# Power_Schematic.net
KiCad netlist of a schematic drawn in EAGLE
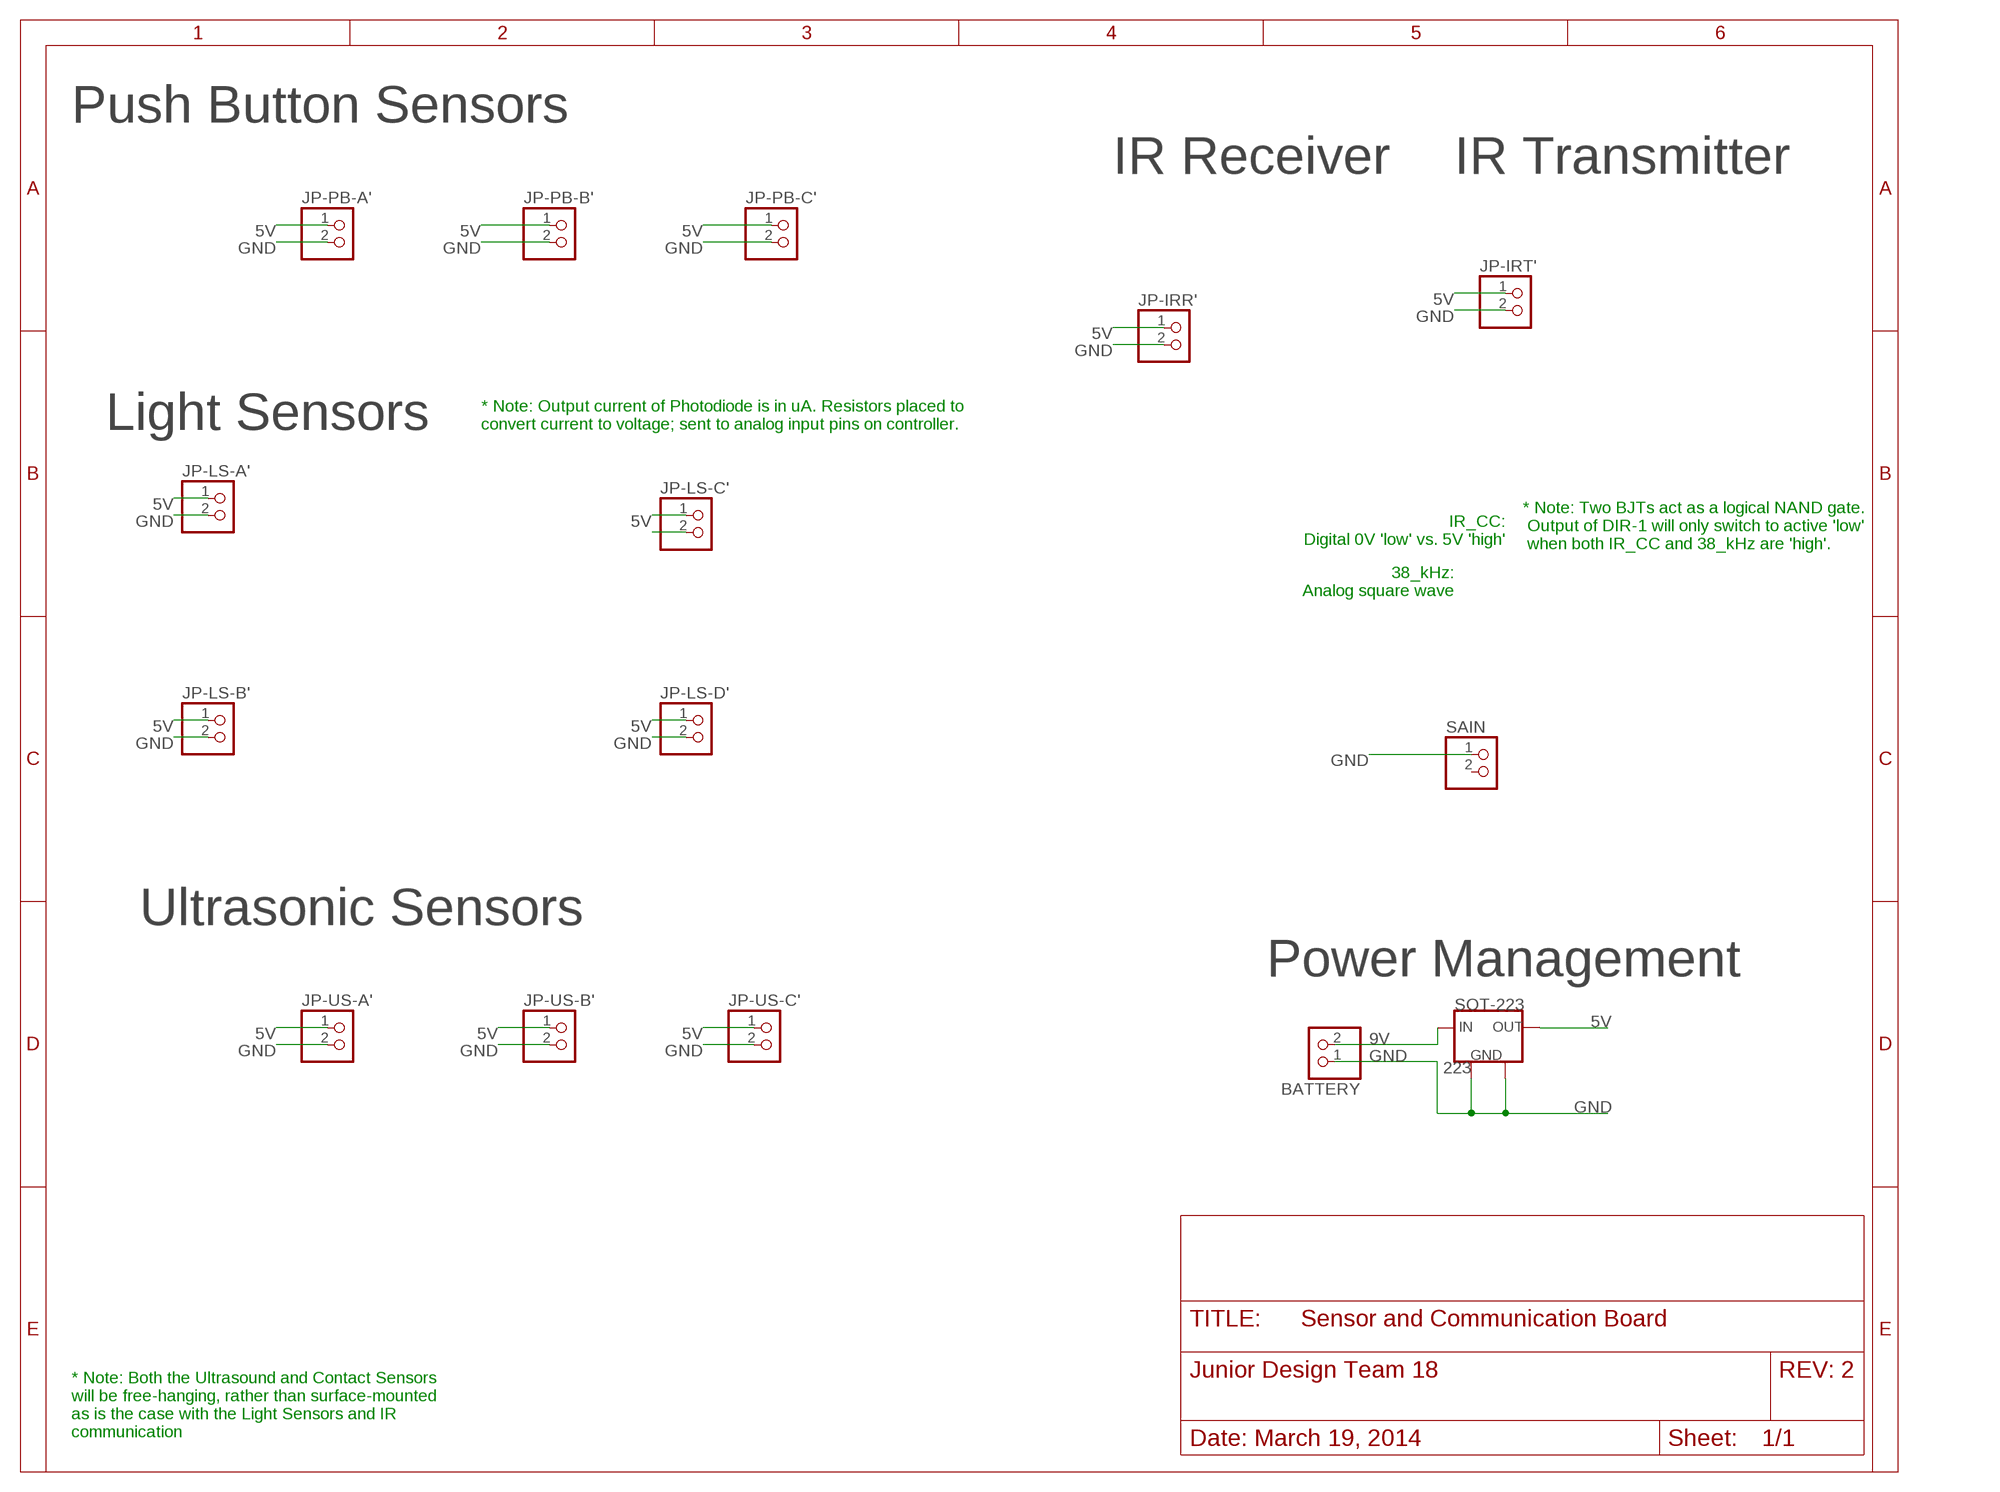
[diagram p0: schematic, sheet 1]

(export (version "E")
  (design (tool "Eeschema 10.0.6"))
  (components
    (comp (ref "BATTERY")
      (value "PINHD-1X2")
      (footprint "eagle-import:1X02")
      (libsource (lib "eagle-import") (part "PINHD-1X2"))
    )
    (comp (ref "JP-IRR'")
      (value "PINHD-1X2")
      (footprint "eagle-import:1X02")
      (libsource (lib "eagle-import") (part "PINHD-1X2"))
    )
    (comp (ref "JP-IRT'")
      (value "PINHD-1X2")
      (footprint "eagle-import:1X02")
      (libsource (lib "eagle-import") (part "PINHD-1X2"))
    )
    (comp (ref "JP-LS-A'")
      (value "PINHD-1X2")
      (footprint "eagle-import:1X02")
      (libsource (lib "eagle-import") (part "PINHD-1X2"))
    )
    (comp (ref "JP-LS-B'")
      (value "PINHD-1X2")
      (footprint "eagle-import:1X02")
      (libsource (lib "eagle-import") (part "PINHD-1X2"))
    )
    (comp (ref "JP-LS-C'")
      (value "PINHD-1X2")
      (footprint "eagle-import:1X02")
      (libsource (lib "eagle-import") (part "PINHD-1X2"))
    )
    (comp (ref "JP-LS-D'")
      (value "PINHD-1X2")
      (footprint "eagle-import:1X02")
      (libsource (lib "eagle-import") (part "PINHD-1X2"))
    )
    (comp (ref "JP-PB-A'")
      (value "PINHD-1X2")
      (footprint "eagle-import:1X02")
      (libsource (lib "eagle-import") (part "PINHD-1X2"))
    )
    (comp (ref "JP-PB-B'")
      (value "PINHD-1X2")
      (footprint "eagle-import:1X02")
      (libsource (lib "eagle-import") (part "PINHD-1X2"))
    )
    (comp (ref "JP-PB-C'")
      (value "PINHD-1X2")
      (footprint "eagle-import:1X02")
      (libsource (lib "eagle-import") (part "PINHD-1X2"))
    )
    (comp (ref "JP-US-A'")
      (value "PINHD-1X2")
      (footprint "eagle-import:1X02")
      (libsource (lib "eagle-import") (part "PINHD-1X2"))
    )
    (comp (ref "JP-US-B'")
      (value "PINHD-1X2")
      (footprint "eagle-import:1X02")
      (libsource (lib "eagle-import") (part "PINHD-1X2"))
    )
    (comp (ref "JP-US-C'")
      (value "PINHD-1X2")
      (footprint "eagle-import:1X02")
      (libsource (lib "eagle-import") (part "PINHD-1X2"))
    )
    (comp (ref "SAIN")
      (value "PINHD-1X2")
      (footprint "eagle-import:1X02")
      (libsource (lib "eagle-import") (part "PINHD-1X2"))
    )
    (comp (ref "SOT-223")
      (value "223")
      (footprint "eagle-import:SOT223")
      (libsource (lib "eagle-import") (part "V_REG_LM1117SOT223"))
    )
  )
  (nets
    (net (code "1") (name "/5V") (class "Default")
      (node (ref "JP-IRR'") (pin "1") (pinfunction "1_1") (pintype "passive"))
      (node (ref "JP-IRT'") (pin "1") (pinfunction "1_1") (pintype "passive"))
      (node (ref "JP-LS-A'") (pin "1") (pinfunction "1_1") (pintype "passive"))
      (node (ref "JP-LS-B'") (pin "1") (pinfunction "1_1") (pintype "passive"))
      (node (ref "JP-LS-C'") (pin "1") (pinfunction "1_1") (pintype "passive"))
      (node (ref "JP-LS-D'") (pin "1") (pinfunction "1_1") (pintype "passive"))
      (node (ref "JP-PB-A'") (pin "1") (pinfunction "1_1") (pintype "passive"))
      (node (ref "JP-PB-B'") (pin "1") (pinfunction "1_1") (pintype "passive"))
      (node (ref "JP-PB-C'") (pin "1") (pinfunction "1_1") (pintype "passive"))
      (node (ref "JP-US-A'") (pin "1") (pinfunction "1_1") (pintype "passive"))
      (node (ref "JP-US-B'") (pin "1") (pinfunction "1_1") (pintype "passive"))
      (node (ref "JP-US-C'") (pin "1") (pinfunction "1_1") (pintype "passive"))
      (node (ref "SOT-223") (pin "GND1") (pinfunction "OUT_GND1") (pintype "output"))
    )
    (net (code "2") (name "/GND") (class "Default")
      (node (ref "BATTERY") (pin "1") (pinfunction "1_1") (pintype "passive"))
      (node (ref "JP-IRR'") (pin "2") (pinfunction "2_2") (pintype "passive"))
      (node (ref "JP-IRT'") (pin "2") (pinfunction "2_2") (pintype "passive"))
      (node (ref "JP-LS-A'") (pin "2") (pinfunction "2_2") (pintype "passive"))
      (node (ref "JP-LS-B'") (pin "2") (pinfunction "2_2") (pintype "passive"))
      (node (ref "JP-LS-C'") (pin "2") (pinfunction "2_2") (pintype "passive"))
      (node (ref "JP-LS-D'") (pin "2") (pinfunction "2_2") (pintype "passive"))
      (node (ref "JP-PB-A'") (pin "2") (pinfunction "2_2") (pintype "passive"))
      (node (ref "JP-PB-B'") (pin "2") (pinfunction "2_2") (pintype "passive"))
      (node (ref "JP-PB-C'") (pin "2") (pinfunction "2_2") (pintype "passive"))
      (node (ref "JP-US-A'") (pin "2") (pinfunction "2_2") (pintype "passive"))
      (node (ref "JP-US-B'") (pin "2") (pinfunction "2_2") (pintype "passive"))
      (node (ref "JP-US-C'") (pin "2") (pinfunction "2_2") (pintype "passive"))
      (node (ref "SAIN") (pin "1") (pinfunction "1_1") (pintype "passive"))
      (node (ref "SOT-223") (pin "GND2") (pinfunction "GND1_GND2") (pintype "output"))
      (node (ref "SOT-223") (pin "IN") (pinfunction "GND2_IN") (pintype "input"))
    )
    (net (code "3") (name "Net-(SOT-223-IN)") (class "Default")
      (node (ref "BATTERY") (pin "2") (pinfunction "2_2") (pintype "passive"))
      (node (ref "SOT-223") (pin "OUT") (pinfunction "IN_OUT") (pintype "input"))
    )
    (net (code "4") (name "unconnected-(SAIN-Pad2)") (class "Default")
      (node (ref "SAIN") (pin "2") (pinfunction "2_2") (pintype "passive"))
    )
  )
)
